# Experiment_2_0_0_0.net
KiCad netlist of a schematic drawn in Altium Designer
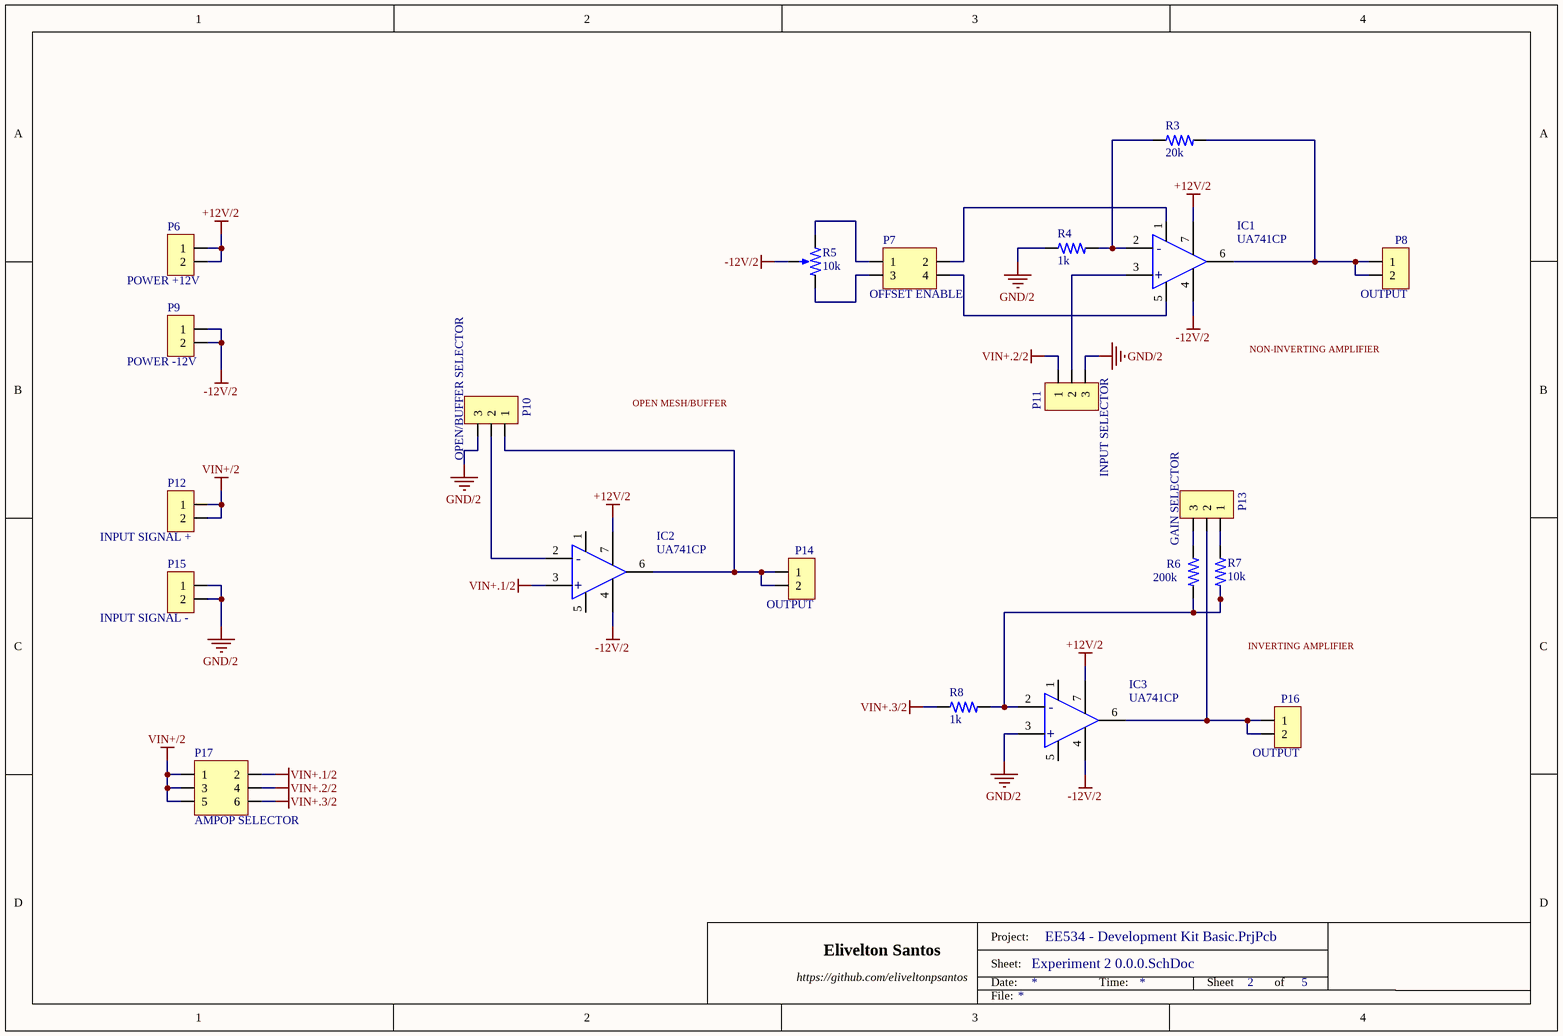
[diagram p0: Experiment 2 0.0.0.SchDoc]

(export (version "E")
  (design (tool "Eeschema 10.0.6"))
  (components
    (comp (ref "IC1")
      (value "UA741CP")
      (footprint "DIP-8")
      (description "IC OPAMP GP 1MHZ 8DIP")
      (fields (field (name "MANUFACTURER") "Texas Instruments"))
      (libsource (lib "ICs") (part "UA741CP"))
    )
    (comp (ref "IC2")
      (value "UA741CP")
      (footprint "DIP-8")
      (description "IC OPAMP GP 1MHZ 8DIP")
      (fields (field (name "MANUFACTURER") "Texas Instruments"))
      (libsource (lib "ICs") (part "UA741CP"))
    )
    (comp (ref "IC3")
      (value "UA741CP")
      (footprint "DIP-8")
      (description "IC OPAMP GP 1MHZ 8DIP")
      (fields (field (name "MANUFACTURER") "Texas Instruments"))
      (libsource (lib "ICs") (part "UA741CP"))
    )
    (comp (ref "P6")
      (value "POWER +12V")
      (footprint "PINHD-1X02 ONCE")
      (description "CONN HEADER 2POS .100\" STR TIN")
      (fields
        (field (name "MANUFACTURER") "Molex, LLC")
        (field (name "MANUFACTURER PART NUMBER") "0901200122")
      )
      (libsource (lib "") (part "PIN HEADER 1X02 ONCE_1"))
    )
    (comp (ref "P7")
      (value "OFFSET ENABLE")
      (footprint "PINHD-2X02")
      (description "CONN HEADER 4POS .100\" STR TIN")
      (fields
        (field (name "MANUFACTURER") "Molex, LLC")
        (field (name "MANUFACTURER PART NUMBER") "0901310122")
      )
      (libsource (lib "Connectors") (part "PIN HEADER 2X02"))
    )
    (comp (ref "P8")
      (value "OUTPUT")
      (footprint "PINHD-1X02 ONCE")
      (description "CONN HEADER 2POS .100\" STR TIN")
      (fields
        (field (name "MANUFACTURER") "Molex, LLC")
        (field (name "MANUFACTURER PART NUMBER") "0901200122")
      )
      (libsource (lib "Connectors") (part "PIN HEADER 1X02 ONCE"))
    )
    (comp (ref "P9")
      (value "POWER -12V")
      (footprint "PINHD-1X02 ONCE")
      (description "CONN HEADER 2POS .100\" STR TIN")
      (fields
        (field (name "MANUFACTURER") "Molex, LLC")
        (field (name "MANUFACTURER PART NUMBER") "0901200122")
      )
      (libsource (lib "") (part "PIN HEADER 1X02 ONCE_1"))
    )
    (comp (ref "P10")
      (value "OPEN/BUFFER SELECTOR")
      (footprint "PINHD-1X03")
      (description "CONN HEADER 3POS .100\" STR TIN")
      (fields
        (field (name "MANUFACTURER") "Molex, LLC")
        (field (name "MANUFACTURER PART NUMBER") "0901200123")
      )
      (libsource (lib "Connectors") (part "PIN HEADER 1X03"))
    )
    (comp (ref "P11")
      (value "INPUT SELECTOR")
      (footprint "PINHD-1X03")
      (description "CONN HEADER 3POS .100\" STR TIN")
      (fields
        (field (name "MANUFACTURER") "Molex, LLC")
        (field (name "MANUFACTURER PART NUMBER") "0901200123")
      )
      (libsource (lib "") (part "PIN HEADER 1X03_1"))
    )
    (comp (ref "P12")
      (value "INPUT SIGNAL +")
      (footprint "PINHD-1X02 ONCE")
      (description "CONN HEADER 2POS .100\" STR TIN")
      (fields
        (field (name "MANUFACTURER") "Molex, LLC")
        (field (name "MANUFACTURER PART NUMBER") "0901200122")
      )
      (libsource (lib "") (part "PIN HEADER 1X02 ONCE_1"))
    )
    (comp (ref "P13")
      (value "GAIN SELECTOR")
      (footprint "PINHD-1X03")
      (description "CONN HEADER 3POS .100\" STR TIN")
      (fields
        (field (name "MANUFACTURER") "Molex, LLC")
        (field (name "MANUFACTURER PART NUMBER") "0901200123")
      )
      (libsource (lib "Connectors") (part "PIN HEADER 1X03"))
    )
    (comp (ref "P14")
      (value "OUTPUT")
      (footprint "PINHD-1X02 ONCE")
      (description "CONN HEADER 2POS .100\" STR TIN")
      (fields
        (field (name "MANUFACTURER") "Molex, LLC")
        (field (name "MANUFACTURER PART NUMBER") "0901200122")
      )
      (libsource (lib "Connectors") (part "PIN HEADER 1X02 ONCE"))
    )
    (comp (ref "P15")
      (value "INPUT SIGNAL -")
      (footprint "PINHD-1X02 ONCE")
      (description "CONN HEADER 2POS .100\" STR TIN")
      (fields
        (field (name "MANUFACTURER") "Molex, LLC")
        (field (name "MANUFACTURER PART NUMBER") "0901200122")
      )
      (libsource (lib "") (part "PIN HEADER 1X02 ONCE_1"))
    )
    (comp (ref "P16")
      (value "OUTPUT")
      (footprint "PINHD-1X02 ONCE")
      (description "CONN HEADER 2POS .100\" STR TIN")
      (fields
        (field (name "MANUFACTURER") "Molex, LLC")
        (field (name "MANUFACTURER PART NUMBER") "0901200122")
      )
      (libsource (lib "Connectors") (part "PIN HEADER 1X02 ONCE"))
    )
    (comp (ref "P17")
      (value "AMPOP SELECTOR")
      (footprint "PINHD-2X03")
      (description "CONN HEADER 6POS .100\" STR TIN")
      (fields
        (field (name "MANUFACTURER") "Molex, LLC")
        (field (name "MANUFACTURER PART NUMBER") "0901310123")
      )
      (libsource (lib "Connectors") (part "PIN HEADER 2X03"))
    )
    (comp (ref "R3")
      (value "20k")
      (footprint "R Axial 0.25")
      (description "RES 20K OHM 1/4W 5% AXIAL")
      (fields
        (field (name "MANUFACTURER") "Yageo")
        (field (name "MANUFACTURER PART NUMBER") "CFR-25JB-52-20K")
      )
      (libsource (lib "Resistors") (part "CFR-25JB-52-20K"))
    )
    (comp (ref "R4")
      (value "1k")
      (footprint "R Axial 0.25")
      (description "RES 1K OHM 1/4W 5% AXIAL")
      (fields
        (field (name "MANUFACTURER") "Yageo")
        (field (name "MANUFACTURER PART NUMBER") "CFR-25JB-52-1K")
      )
      (libsource (lib "Resistors") (part "CFR-25JB-52-1K"))
    )
    (comp (ref "R5")
      (value "10k")
      (footprint "PV36W")
      (description "TRIMMER 10K OHM 0.5W TH")
      (fields
        (field (name "MANUFACTURER") "Bourns Inc.")
        (field (name "MANUFACTURER PART NUMBER") "PV36W103C01B00")
      )
      (libsource (lib "Resistors") (part "PV36W103C01B00"))
    )
    (comp (ref "R6")
      (value "200k")
      (footprint "R Axial 0.25")
      (description "RES 200K OHM 1/4W 5% AXIAL")
      (fields
        (field (name "MANUFACTURER") "Yageo")
        (field (name "MANUFACTURER PART NUMBER") "CFR-25JB-52-200K")
      )
      (libsource (lib "Resistors") (part "CFR-25JB-52-200K"))
    )
    (comp (ref "R7")
      (value "10k")
      (footprint "R Axial 0.25")
      (description "RES 10K OHM 1/4W 5% AXIAL")
      (fields
        (field (name "MANUFACTURER") "Yageo")
        (field (name "MANUFACTURER PART NUMBER") "CFR-25JB-52-10K")
      )
      (libsource (lib "Resistors") (part "CFR-25JB-52-10K"))
    )
    (comp (ref "R8")
      (value "1k")
      (footprint "R Axial 0.25")
      (description "RES 1K OHM 1/4W 5% AXIAL")
      (fields
        (field (name "MANUFACTURER") "Yageo")
        (field (name "MANUFACTURER PART NUMBER") "CFR-25JB-52-1K")
      )
      (libsource (lib "Resistors") (part "CFR-25JB-52-1K"))
    )
  )
  (nets
    (net (code "1") (name "+12V{slash}2") (class "Default")
      (node (ref "IC1") (pin "7") (pinfunction "VCC+_7") (pintype "power_in"))
      (node (ref "IC2") (pin "7") (pinfunction "VCC+_7") (pintype "power_in"))
      (node (ref "IC3") (pin "7") (pinfunction "VCC+_7") (pintype "power_in"))
      (node (ref "P6") (pin "1") (pinfunction "1_1") (pintype "passive"))
      (node (ref "P6") (pin "2") (pinfunction "2_2") (pintype "passive"))
    )
    (net (code "2") (name "-12V{slash}2") (class "Default")
      (node (ref "IC1") (pin "4") (pinfunction "VCC-_4") (pintype "power_in"))
      (node (ref "IC2") (pin "4") (pinfunction "VCC-_4") (pintype "power_in"))
      (node (ref "IC3") (pin "4") (pinfunction "VCC-_4") (pintype "power_in"))
      (node (ref "P9") (pin "1") (pinfunction "1_1") (pintype "passive"))
      (node (ref "P9") (pin "2") (pinfunction "2_2") (pintype "passive"))
      (node (ref "R5") (pin "2") (pinfunction "2_2") (pintype "passive"))
    )
    (net (code "3") (name "GND{slash}2") (class "Default")
      (node (ref "IC3") (pin "3") (pinfunction "+_3") (pintype "passive"))
      (node (ref "P10") (pin "3") (pinfunction "3_3") (pintype "passive"))
      (node (ref "P11") (pin "3") (pinfunction "3_3") (pintype "passive"))
      (node (ref "P15") (pin "1") (pinfunction "1_1") (pintype "passive"))
      (node (ref "P15") (pin "2") (pinfunction "2_2") (pintype "passive"))
      (node (ref "R4") (pin "1") (pinfunction "1_1") (pintype "passive"))
    )
    (net (code "4") (name "Net-(IC1-+)") (class "Default")
      (node (ref "IC1") (pin "3") (pinfunction "+_3") (pintype "passive"))
      (node (ref "P11") (pin "2") (pinfunction "2_2") (pintype "passive"))
    )
    (net (code "5") (name "Net-(IC1--)") (class "Default")
      (node (ref "IC1") (pin "2") (pinfunction "-_2") (pintype "passive"))
      (node (ref "R3") (pin "1") (pinfunction "1_1") (pintype "passive"))
      (node (ref "R4") (pin "2") (pinfunction "2_2") (pintype "passive"))
    )
    (net (code "6") (name "Net-(IC1-OFFSET1)") (class "Default")
      (node (ref "IC1") (pin "1") (pinfunction "OFFSET1_1") (pintype "passive"))
      (node (ref "P7") (pin "2") (pinfunction "2_2") (pintype "passive"))
    )
    (net (code "7") (name "Net-(IC1-OFFSET2)") (class "Default")
      (node (ref "IC1") (pin "5") (pinfunction "OFFSET2_5") (pintype "passive"))
      (node (ref "P7") (pin "4") (pinfunction "4_4") (pintype "passive"))
    )
    (net (code "8") (name "Net-(IC1-OUTPUT)") (class "Default")
      (node (ref "IC1") (pin "6") (pinfunction "OUTPUT_6") (pintype "passive"))
      (node (ref "P8") (pin "1") (pinfunction "1_1") (pintype "passive"))
      (node (ref "P8") (pin "2") (pinfunction "2_2") (pintype "passive"))
      (node (ref "R3") (pin "2") (pinfunction "2_2") (pintype "passive"))
    )
    (net (code "9") (name "Net-(IC2--)") (class "Default")
      (node (ref "IC2") (pin "2") (pinfunction "-_2") (pintype "passive"))
      (node (ref "P10") (pin "2") (pinfunction "2_2") (pintype "passive"))
    )
    (net (code "10") (name "Net-(IC2-OUTPUT)") (class "Default")
      (node (ref "IC2") (pin "6") (pinfunction "OUTPUT_6") (pintype "passive"))
      (node (ref "P10") (pin "1") (pinfunction "1_1") (pintype "passive"))
      (node (ref "P14") (pin "1") (pinfunction "1_1") (pintype "passive"))
      (node (ref "P14") (pin "2") (pinfunction "2_2") (pintype "passive"))
    )
    (net (code "11") (name "Net-(IC3--)") (class "Default")
      (node (ref "IC3") (pin "2") (pinfunction "-_2") (pintype "passive"))
      (node (ref "R6") (pin "1") (pinfunction "1_1") (pintype "passive"))
      (node (ref "R7") (pin "2") (pinfunction "2_2") (pintype "passive"))
      (node (ref "R8") (pin "2") (pinfunction "2_2") (pintype "passive"))
    )
    (net (code "12") (name "Net-(IC3-OUTPUT)") (class "Default")
      (node (ref "IC3") (pin "6") (pinfunction "OUTPUT_6") (pintype "passive"))
      (node (ref "P13") (pin "2") (pinfunction "2_2") (pintype "passive"))
      (node (ref "P16") (pin "1") (pinfunction "1_1") (pintype "passive"))
      (node (ref "P16") (pin "2") (pinfunction "2_2") (pintype "passive"))
    )
    (net (code "13") (name "Net-(P7-Pad1)") (class "Default")
      (node (ref "P7") (pin "1") (pinfunction "1_1") (pintype "passive"))
      (node (ref "R5") (pin "1") (pinfunction "1_1") (pintype "passive"))
    )
    (net (code "14") (name "Net-(P7-Pad3)") (class "Default")
      (node (ref "P7") (pin "3") (pinfunction "3_3") (pintype "passive"))
      (node (ref "R5") (pin "3") (pinfunction "3_3") (pintype "passive"))
    )
    (net (code "15") (name "Net-(P13-Pad1)") (class "Default")
      (node (ref "P13") (pin "1") (pinfunction "1_1") (pintype "passive"))
      (node (ref "R7") (pin "1") (pinfunction "1_1") (pintype "passive"))
    )
    (net (code "16") (name "Net-(P13-Pad3)") (class "Default")
      (node (ref "P13") (pin "3") (pinfunction "3_3") (pintype "passive"))
      (node (ref "R6") (pin "2") (pinfunction "2_2") (pintype "passive"))
    )
    (net (code "17") (name "VIN+.1{slash}2") (class "Default")
      (node (ref "IC2") (pin "3") (pinfunction "+_3") (pintype "passive"))
      (node (ref "P17") (pin "2") (pinfunction "2_2") (pintype "passive"))
    )
    (net (code "18") (name "VIN+.2{slash}2") (class "Default")
      (node (ref "P11") (pin "1") (pinfunction "1_1") (pintype "passive"))
      (node (ref "P17") (pin "4") (pinfunction "4_4") (pintype "passive"))
    )
    (net (code "19") (name "VIN+.3{slash}2") (class "Default")
      (node (ref "P17") (pin "6") (pinfunction "6_6") (pintype "passive"))
      (node (ref "R8") (pin "1") (pinfunction "1_1") (pintype "passive"))
    )
    (net (code "20") (name "VIN+{slash}2") (class "Default")
      (node (ref "P12") (pin "1") (pinfunction "1_1") (pintype "passive"))
      (node (ref "P12") (pin "2") (pinfunction "2_2") (pintype "passive"))
      (node (ref "P17") (pin "1") (pinfunction "1_1") (pintype "passive"))
      (node (ref "P17") (pin "3") (pinfunction "3_3") (pintype "passive"))
      (node (ref "P17") (pin "5") (pinfunction "5_5") (pintype "passive"))
    )
    (net (code "21") (name "unconnected-(IC2-OFFSET1-Pad1)") (class "Default")
      (node (ref "IC2") (pin "1") (pinfunction "OFFSET1_1") (pintype "passive"))
    )
    (net (code "22") (name "unconnected-(IC2-OFFSET2-Pad5)") (class "Default")
      (node (ref "IC2") (pin "5") (pinfunction "OFFSET2_5") (pintype "passive"))
    )
    (net (code "23") (name "unconnected-(IC3-OFFSET1-Pad1)") (class "Default")
      (node (ref "IC3") (pin "1") (pinfunction "OFFSET1_1") (pintype "passive"))
    )
    (net (code "24") (name "unconnected-(IC3-OFFSET2-Pad5)") (class "Default")
      (node (ref "IC3") (pin "5") (pinfunction "OFFSET2_5") (pintype "passive"))
    )
  )
)
